# spi_v2.net
KiCad netlist of a schematic drawn in EAGLE
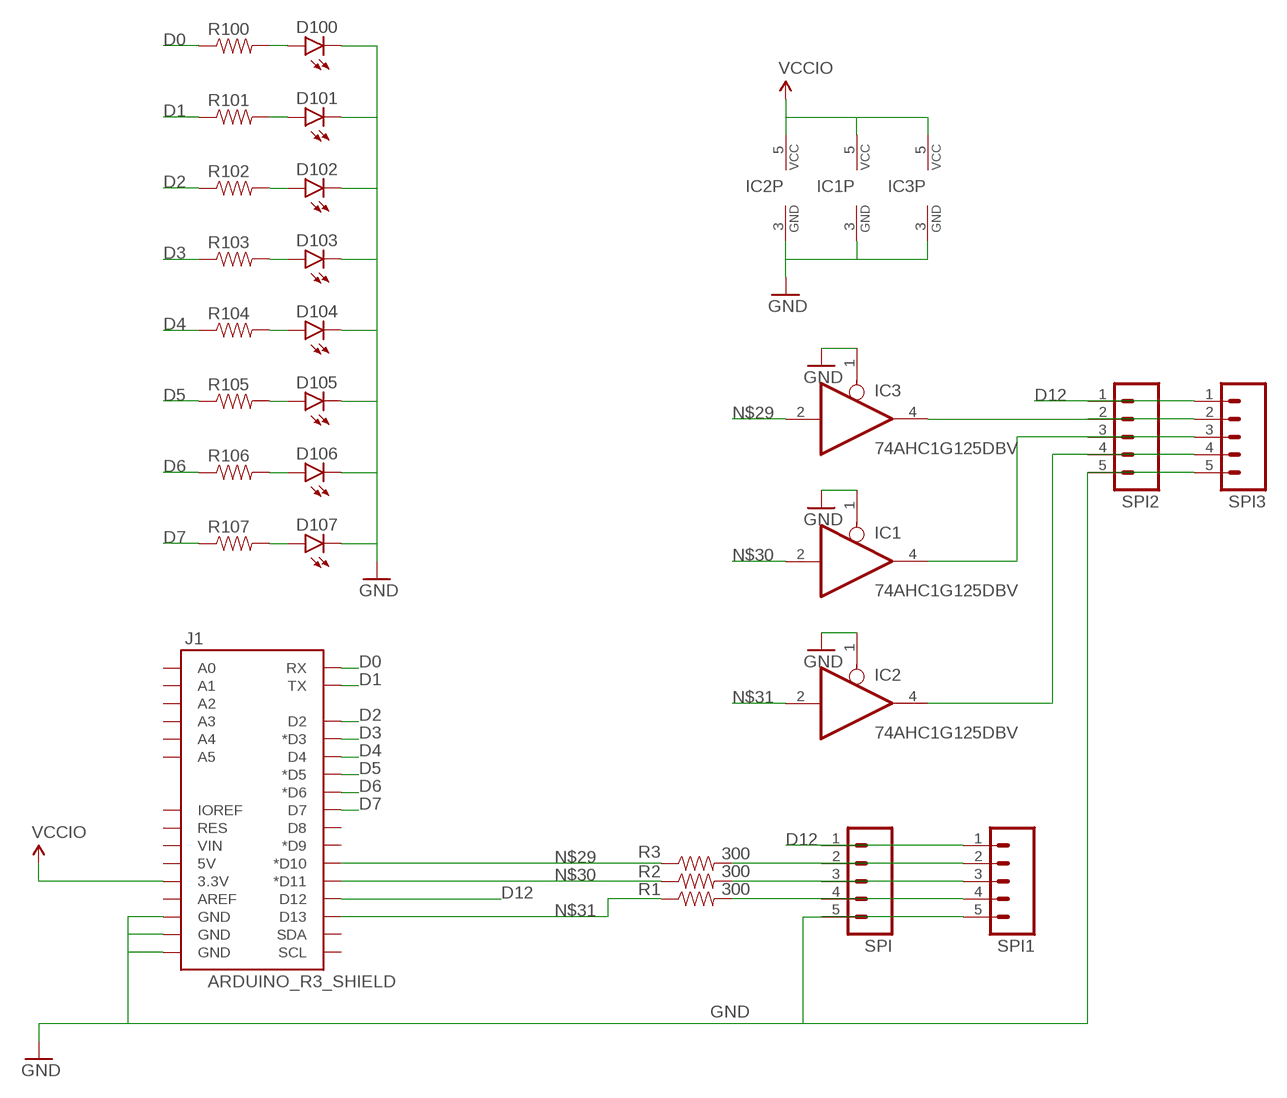
[diagram p0: schematic, sheet 1]

(export (version "E")
  (design (tool "Eeschema 10.0.6"))
  (components
    (comp (ref "D100")
      (value "LED-FKIT-1206")
      (footprint "eagle-import:FKIT-LED-1206")
      (libsource (lib "eagle-import") (part "LED-FKIT-1206"))
    )
    (comp (ref "D101")
      (value "LED-FKIT-1206")
      (footprint "eagle-import:FKIT-LED-1206")
      (libsource (lib "eagle-import") (part "LED-FKIT-1206"))
    )
    (comp (ref "D102")
      (value "LED-FKIT-1206")
      (footprint "eagle-import:FKIT-LED-1206")
      (libsource (lib "eagle-import") (part "LED-FKIT-1206"))
    )
    (comp (ref "D103")
      (value "LED-FKIT-1206")
      (footprint "eagle-import:FKIT-LED-1206")
      (libsource (lib "eagle-import") (part "LED-FKIT-1206"))
    )
    (comp (ref "D104")
      (value "LED-FKIT-1206")
      (footprint "eagle-import:FKIT-LED-1206")
      (libsource (lib "eagle-import") (part "LED-FKIT-1206"))
    )
    (comp (ref "D105")
      (value "LED-FKIT-1206")
      (footprint "eagle-import:FKIT-LED-1206")
      (libsource (lib "eagle-import") (part "LED-FKIT-1206"))
    )
    (comp (ref "D106")
      (value "LED-FKIT-1206")
      (footprint "eagle-import:FKIT-LED-1206")
      (libsource (lib "eagle-import") (part "LED-FKIT-1206"))
    )
    (comp (ref "D107")
      (value "LED-FKIT-1206")
      (footprint "eagle-import:FKIT-LED-1206")
      (libsource (lib "eagle-import") (part "LED-FKIT-1206"))
    )
    (comp (ref "IC1")
      (value "74AHC1G125DBV")
      (footprint "eagle-import:SOT23-5")
      (libsource (lib "eagle-import") (part "741G125DBVAHC"))
    )
    (comp (ref "IC2")
      (value "74AHC1G125DBV")
      (footprint "eagle-import:SOT23-5")
      (libsource (lib "eagle-import") (part "741G125DBVAHC"))
    )
    (comp (ref "IC3")
      (value "74AHC1G125DBV")
      (footprint "eagle-import:SOT23-5")
      (libsource (lib "eagle-import") (part "741G125DBVAHC"))
    )
    (comp (ref "J1")
      (value "ARDUINO_R3_SHIELD")
      (footprint "eagle-import:UNO_R3_SHIELD")
      (libsource (lib "eagle-import") (part "ARDUINO_R3_SHIELD"))
    )
    (comp (ref "R1")
      (value "300")
      (footprint "eagle-import:AXIAL-0.4")
      (libsource (lib "eagle-import") (part "RESISTORPTH-1/4W"))
    )
    (comp (ref "R2")
      (value "300")
      (footprint "eagle-import:AXIAL-0.4")
      (libsource (lib "eagle-import") (part "RESISTORPTH-1/4W"))
    )
    (comp (ref "R3")
      (value "300")
      (footprint "eagle-import:AXIAL-0.4")
      (libsource (lib "eagle-import") (part "RESISTORPTH-1/4W"))
    )
    (comp (ref "R100")
      (value "RESISTOR0805-RES")
      (footprint "eagle-import:0805")
      (libsource (lib "eagle-import") (part "RESISTOR0805-RES"))
    )
    (comp (ref "R101")
      (value "RESISTOR0805-RES")
      (footprint "eagle-import:0805")
      (libsource (lib "eagle-import") (part "RESISTOR0805-RES"))
    )
    (comp (ref "R102")
      (value "RESISTOR0805-RES")
      (footprint "eagle-import:0805")
      (libsource (lib "eagle-import") (part "RESISTOR0805-RES"))
    )
    (comp (ref "R103")
      (value "RESISTOR0805-RES")
      (footprint "eagle-import:0805")
      (libsource (lib "eagle-import") (part "RESISTOR0805-RES"))
    )
    (comp (ref "R104")
      (value "RESISTOR0805-RES")
      (footprint "eagle-import:0805")
      (libsource (lib "eagle-import") (part "RESISTOR0805-RES"))
    )
    (comp (ref "R105")
      (value "RESISTOR0805-RES")
      (footprint "eagle-import:0805")
      (libsource (lib "eagle-import") (part "RESISTOR0805-RES"))
    )
    (comp (ref "R106")
      (value "RESISTOR0805-RES")
      (footprint "eagle-import:0805")
      (libsource (lib "eagle-import") (part "RESISTOR0805-RES"))
    )
    (comp (ref "R107")
      (value "RESISTOR0805-RES")
      (footprint "eagle-import:0805")
      (libsource (lib "eagle-import") (part "RESISTOR0805-RES"))
    )
    (comp (ref "SPI")
      (value "M05PTH_LONGPADS")
      (footprint "eagle-import:1X05_LONGPADS")
      (libsource (lib "eagle-import") (part "M05PTH_LONGPADS"))
    )
    (comp (ref "SPI1")
      (value "M05PTH_LONGPADS")
      (footprint "eagle-import:1X05_LONGPADS")
      (libsource (lib "eagle-import") (part "M05PTH_LONGPADS"))
    )
    (comp (ref "SPI2")
      (value "M05PTH_LONGPADS")
      (footprint "eagle-import:1X05_LONGPADS")
      (libsource (lib "eagle-import") (part "M05PTH_LONGPADS"))
    )
    (comp (ref "SPI3")
      (value "M05PTH_LONGPADS")
      (footprint "eagle-import:1X05_LONGPADS")
      (libsource (lib "eagle-import") (part "M05PTH_LONGPADS"))
    )
  )
  (nets
    (net (code "1") (name "/D0") (class "Default")
      (node (ref "J1") (pin "RX") (pinfunction "RX_RX") (pintype "bidirectional"))
      (node (ref "R100") (pin "1") (pinfunction "1_1") (pintype "passive"))
    )
    (net (code "2") (name "/D1") (class "Default")
      (node (ref "J1") (pin "TX") (pinfunction "TX_TX") (pintype "bidirectional"))
      (node (ref "R101") (pin "1") (pinfunction "1_1") (pintype "passive"))
    )
    (net (code "3") (name "/D2") (class "Default")
      (node (ref "J1") (pin "D2") (pinfunction "D2_D2") (pintype "bidirectional"))
      (node (ref "R102") (pin "1") (pinfunction "1_1") (pintype "passive"))
    )
    (net (code "4") (name "/D3") (class "Default")
      (node (ref "J1") (pin "D3") (pinfunction "*D3_D3") (pintype "bidirectional"))
      (node (ref "R103") (pin "1") (pinfunction "1_1") (pintype "passive"))
    )
    (net (code "5") (name "/D4") (class "Default")
      (node (ref "J1") (pin "D4") (pinfunction "D4_D4") (pintype "bidirectional"))
      (node (ref "R104") (pin "1") (pinfunction "1_1") (pintype "passive"))
    )
    (net (code "6") (name "/D5") (class "Default")
      (node (ref "J1") (pin "D5") (pinfunction "*D5_D5") (pintype "bidirectional"))
      (node (ref "R105") (pin "1") (pinfunction "1_1") (pintype "passive"))
    )
    (net (code "7") (name "/D6") (class "Default")
      (node (ref "J1") (pin "D6") (pinfunction "*D6_D6") (pintype "bidirectional"))
      (node (ref "R106") (pin "1") (pinfunction "1_1") (pintype "passive"))
    )
    (net (code "8") (name "/D7") (class "Default")
      (node (ref "J1") (pin "D7") (pinfunction "D7_D7") (pintype "bidirectional"))
      (node (ref "R107") (pin "1") (pinfunction "1_1") (pintype "passive"))
    )
    (net (code "9") (name "/D12") (class "Default")
      (node (ref "J1") (pin "D12") (pinfunction "D12_D12") (pintype "bidirectional"))
      (node (ref "SPI") (pin "1") (pinfunction "1_1") (pintype "passive"))
      (node (ref "SPI1") (pin "1") (pinfunction "1_1") (pintype "passive"))
      (node (ref "SPI2") (pin "1") (pinfunction "1_1") (pintype "passive"))
      (node (ref "SPI3") (pin "1") (pinfunction "1_1") (pintype "passive"))
    )
    (net (code "10") (name "/N$29") (class "Default")
      (node (ref "IC3") (pin "2") (pinfunction "I_2") (pintype "input"))
      (node (ref "J1") (pin "D10") (pinfunction "*D10_D10") (pintype "bidirectional"))
      (node (ref "R3") (pin "P$1") (pinfunction "1_P$1") (pintype "passive"))
    )
    (net (code "11") (name "/N$30") (class "Default")
      (node (ref "IC1") (pin "2") (pinfunction "I_2") (pintype "input"))
      (node (ref "J1") (pin "D11") (pinfunction "*D11_D11") (pintype "bidirectional"))
      (node (ref "R2") (pin "P$1") (pinfunction "1_P$1") (pintype "passive"))
    )
    (net (code "12") (name "/N$31") (class "Default")
      (node (ref "IC2") (pin "2") (pinfunction "I_2") (pintype "input"))
      (node (ref "J1") (pin "D13") (pinfunction "D13_D13") (pintype "bidirectional"))
      (node (ref "R1") (pin "P$1") (pinfunction "1_P$1") (pintype "passive"))
    )
    (net (code "13") (name "GND") (class "Default")
      (node (ref "D100") (pin "C") (pinfunction "C_C") (pintype "passive"))
      (node (ref "D101") (pin "C") (pinfunction "C_C") (pintype "passive"))
      (node (ref "D102") (pin "C") (pinfunction "C_C") (pintype "passive"))
      (node (ref "D103") (pin "C") (pinfunction "C_C") (pintype "passive"))
      (node (ref "D104") (pin "C") (pinfunction "C_C") (pintype "passive"))
      (node (ref "D105") (pin "C") (pinfunction "C_C") (pintype "passive"))
      (node (ref "D106") (pin "C") (pinfunction "C_C") (pintype "passive"))
      (node (ref "D107") (pin "C") (pinfunction "C_C") (pintype "passive"))
      (node (ref "IC1") (pin "1") (pinfunction "OE_1") (pintype "input"))
      (node (ref "IC1") (pin "3") (pinfunction "GND_3") (pintype "power_in"))
      (node (ref "IC2") (pin "1") (pinfunction "OE_1") (pintype "input"))
      (node (ref "IC2") (pin "3") (pinfunction "GND_3") (pintype "power_in"))
      (node (ref "IC3") (pin "1") (pinfunction "OE_1") (pintype "input"))
      (node (ref "IC3") (pin "3") (pinfunction "GND_3") (pintype "power_in"))
      (node (ref "J1") (pin "GND@0") (pinfunction "GND_GND@0") (pintype "bidirectional"))
      (node (ref "J1") (pin "GND@1") (pinfunction "GND_GND@1") (pintype "bidirectional"))
      (node (ref "J1") (pin "GND@2") (pinfunction "GND_GND@2") (pintype "bidirectional"))
      (node (ref "SPI") (pin "5") (pinfunction "5_5") (pintype "passive"))
      (node (ref "SPI1") (pin "5") (pinfunction "5_5") (pintype "passive"))
      (node (ref "SPI2") (pin "5") (pinfunction "5_5") (pintype "passive"))
      (node (ref "SPI3") (pin "5") (pinfunction "5_5") (pintype "passive"))
    )
    (net (code "14") (name "Net-(D100-PadA)") (class "Default")
      (node (ref "D100") (pin "A") (pinfunction "A_A") (pintype "passive"))
      (node (ref "R100") (pin "2") (pinfunction "2_2") (pintype "passive"))
    )
    (net (code "15") (name "Net-(D101-PadA)") (class "Default")
      (node (ref "D101") (pin "A") (pinfunction "A_A") (pintype "passive"))
      (node (ref "R101") (pin "2") (pinfunction "2_2") (pintype "passive"))
    )
    (net (code "16") (name "Net-(D102-PadA)") (class "Default")
      (node (ref "D102") (pin "A") (pinfunction "A_A") (pintype "passive"))
      (node (ref "R102") (pin "2") (pinfunction "2_2") (pintype "passive"))
    )
    (net (code "17") (name "Net-(D103-PadA)") (class "Default")
      (node (ref "D103") (pin "A") (pinfunction "A_A") (pintype "passive"))
      (node (ref "R103") (pin "2") (pinfunction "2_2") (pintype "passive"))
    )
    (net (code "18") (name "Net-(D104-PadA)") (class "Default")
      (node (ref "D104") (pin "A") (pinfunction "A_A") (pintype "passive"))
      (node (ref "R104") (pin "2") (pinfunction "2_2") (pintype "passive"))
    )
    (net (code "19") (name "Net-(D105-PadA)") (class "Default")
      (node (ref "D105") (pin "A") (pinfunction "A_A") (pintype "passive"))
      (node (ref "R105") (pin "2") (pinfunction "2_2") (pintype "passive"))
    )
    (net (code "20") (name "Net-(D106-PadA)") (class "Default")
      (node (ref "D106") (pin "A") (pinfunction "A_A") (pintype "passive"))
      (node (ref "R106") (pin "2") (pinfunction "2_2") (pintype "passive"))
    )
    (net (code "21") (name "Net-(D107-PadA)") (class "Default")
      (node (ref "D107") (pin "A") (pinfunction "A_A") (pintype "passive"))
      (node (ref "R107") (pin "2") (pinfunction "2_2") (pintype "passive"))
    )
    (net (code "22") (name "Net-(IC1A-O)") (class "Default")
      (node (ref "IC1") (pin "4") (pinfunction "O_4") (pintype "tri_state"))
      (node (ref "SPI2") (pin "3") (pinfunction "3_3") (pintype "passive"))
      (node (ref "SPI3") (pin "3") (pinfunction "3_3") (pintype "passive"))
    )
    (net (code "23") (name "Net-(IC2A-O)") (class "Default")
      (node (ref "IC2") (pin "4") (pinfunction "O_4") (pintype "tri_state"))
      (node (ref "SPI2") (pin "4") (pinfunction "4_4") (pintype "passive"))
      (node (ref "SPI3") (pin "4") (pinfunction "4_4") (pintype "passive"))
    )
    (net (code "24") (name "Net-(IC3A-O)") (class "Default")
      (node (ref "IC3") (pin "4") (pinfunction "O_4") (pintype "tri_state"))
      (node (ref "SPI2") (pin "2") (pinfunction "2_2") (pintype "passive"))
      (node (ref "SPI3") (pin "2") (pinfunction "2_2") (pintype "passive"))
    )
    (net (code "25") (name "Net-(R1-2)") (class "Default")
      (node (ref "R1") (pin "P$2") (pinfunction "2_P$2") (pintype "passive"))
      (node (ref "SPI") (pin "4") (pinfunction "4_4") (pintype "passive"))
      (node (ref "SPI1") (pin "4") (pinfunction "4_4") (pintype "passive"))
    )
    (net (code "26") (name "Net-(R2-2)") (class "Default")
      (node (ref "R2") (pin "P$2") (pinfunction "2_P$2") (pintype "passive"))
      (node (ref "SPI") (pin "3") (pinfunction "3_3") (pintype "passive"))
      (node (ref "SPI1") (pin "3") (pinfunction "3_3") (pintype "passive"))
    )
    (net (code "27") (name "Net-(R3-2)") (class "Default")
      (node (ref "R3") (pin "P$2") (pinfunction "2_P$2") (pintype "passive"))
      (node (ref "SPI") (pin "2") (pinfunction "2_2") (pintype "passive"))
      (node (ref "SPI1") (pin "2") (pinfunction "2_2") (pintype "passive"))
    )
    (net (code "28") (name "VCCIO") (class "Default")
      (node (ref "IC1") (pin "5") (pinfunction "VCC_5") (pintype "power_in"))
      (node (ref "IC2") (pin "5") (pinfunction "VCC_5") (pintype "power_in"))
      (node (ref "IC3") (pin "5") (pinfunction "VCC_5") (pintype "power_in"))
      (node (ref "J1") (pin "3.3V") (pinfunction "3.3V_3.3V") (pintype "bidirectional"))
    )
    (net (code "29") (name "unconnected-(J1-*D9-PadD9)") (class "Default")
      (node (ref "J1") (pin "D9") (pinfunction "*D9_D9") (pintype "bidirectional"))
    )
    (net (code "30") (name "unconnected-(J1-Pad5V)") (class "Default")
      (node (ref "J1") (pin "5V") (pinfunction "5V_5V") (pintype "bidirectional"))
    )
    (net (code "31") (name "unconnected-(J1-PadA0)") (class "Default")
      (node (ref "J1") (pin "A0") (pinfunction "A0_A0") (pintype "bidirectional"))
    )
    (net (code "32") (name "unconnected-(J1-PadA1)") (class "Default")
      (node (ref "J1") (pin "A1") (pinfunction "A1_A1") (pintype "bidirectional"))
    )
    (net (code "33") (name "unconnected-(J1-PadA2)") (class "Default")
      (node (ref "J1") (pin "A2") (pinfunction "A2_A2") (pintype "bidirectional"))
    )
    (net (code "34") (name "unconnected-(J1-PadA3)") (class "Default")
      (node (ref "J1") (pin "A3") (pinfunction "A3_A3") (pintype "bidirectional"))
    )
    (net (code "35") (name "unconnected-(J1-PadA4)") (class "Default")
      (node (ref "J1") (pin "A4") (pinfunction "A4_A4") (pintype "bidirectional"))
    )
    (net (code "36") (name "unconnected-(J1-PadA5)") (class "Default")
      (node (ref "J1") (pin "A5") (pinfunction "A5_A5") (pintype "bidirectional"))
    )
    (net (code "37") (name "unconnected-(J1-PadAREF)") (class "Default")
      (node (ref "J1") (pin "AREF") (pinfunction "AREF_AREF") (pintype "bidirectional"))
    )
    (net (code "38") (name "unconnected-(J1-PadD8)") (class "Default")
      (node (ref "J1") (pin "D8") (pinfunction "D8_D8") (pintype "bidirectional"))
    )
    (net (code "39") (name "unconnected-(J1-PadIOREF)") (class "Default")
      (node (ref "J1") (pin "IOREF") (pinfunction "IOREF_IOREF") (pintype "bidirectional"))
    )
    (net (code "40") (name "unconnected-(J1-PadRES)") (class "Default")
      (node (ref "J1") (pin "RES") (pinfunction "RES_RES") (pintype "bidirectional"))
    )
    (net (code "41") (name "unconnected-(J1-PadSCL)") (class "Default")
      (node (ref "J1") (pin "SCL") (pinfunction "SCL_SCL") (pintype "bidirectional"))
    )
    (net (code "42") (name "unconnected-(J1-PadSDA)") (class "Default")
      (node (ref "J1") (pin "SDA") (pinfunction "SDA_SDA") (pintype "bidirectional"))
    )
    (net (code "43") (name "unconnected-(J1-PadVIN)") (class "Default")
      (node (ref "J1") (pin "VIN") (pinfunction "VIN_VIN") (pintype "bidirectional"))
    )
  )
)
